# Power.net
KiCad netlist of a schematic drawn in Altium Designer
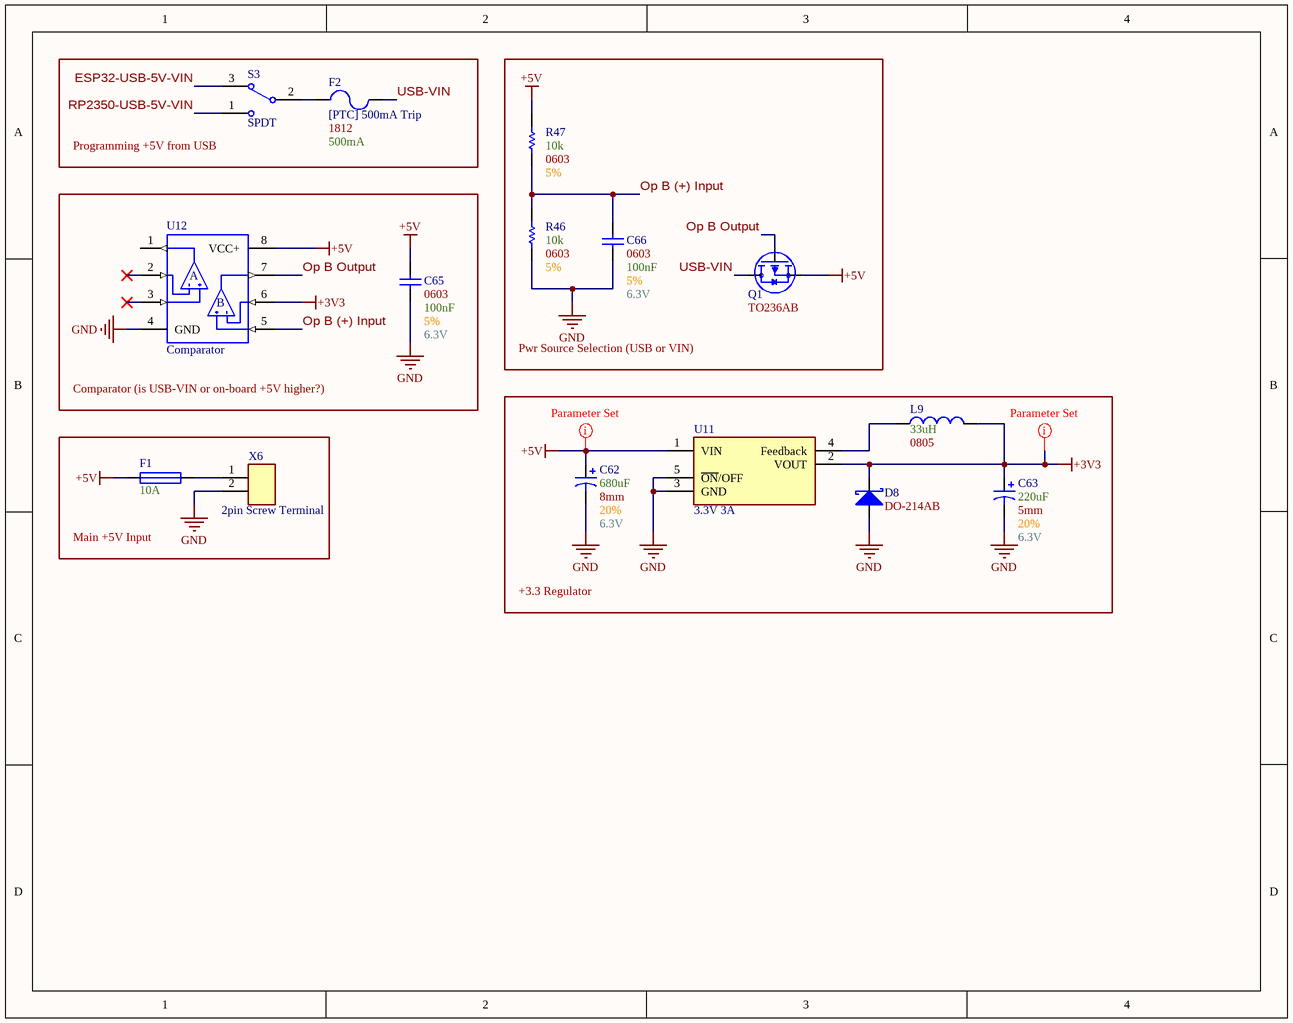
[diagram p0: Power.SchDoc]

(export (version "E")
  (design (tool "Eeschema 10.0.6"))
  (components
    (comp (ref "C62")
      (value "SMD Polarized")
      (footprint "[Cap] SMD Polarized, 8mm")
      (fields
        (field (name "TOLERANCE") "20%")
        (field (name "MAX VOLTAGE") "6.3V")
        (field (name "CAPACITANCE") "680uF")
        (field (name "DIAMETER") "8mm")
      )
      (libsource (lib "RADM Components") (part "[Cap] SMD Polarized"))
    )
    (comp (ref "C63")
      (value "SMD Polarized")
      (footprint "[Cap] SMD Polarized, 5mm")
      (fields
        (field (name "TOLERANCE") "20%")
        (field (name "MAX VOLTAGE") "6.3V")
        (field (name "CAPACITANCE") "220uF")
        (field (name "DIAMETER") "5mm")
      )
      (libsource (lib "RADM Components") (part "[Cap] SMD Polarized"))
    )
    (comp (ref "C65")
      (value "[Cap] SMD Nonpolarized")
      (footprint "[Cap] SMD 0603")
      (fields
        (field (name "SIZE PACKAGE") "0603")
        (field (name "CAPACITANCE") "100nF")
        (field (name "VOLTAGE") "6.3V")
        (field (name "TOLERANCE") "5%")
      )
      (libsource (lib "RADM Components") (part "[Cap] SMD Nonpolarized"))
    )
    (comp (ref "C66")
      (value "[Cap] SMD Nonpolarized")
      (footprint "[Cap] SMD 0603")
      (fields
        (field (name "SIZE PACKAGE") "0603")
        (field (name "CAPACITANCE") "100nF")
        (field (name "VOLTAGE") "6.3V")
        (field (name "TOLERANCE") "5%")
      )
      (libsource (lib "RADM Components") (part "[Cap] SMD Nonpolarized"))
    )
    (comp (ref "D8")
      (value "Schottky")
      (footprint "[Diode] SMD DO-214AB")
      (description "Generic")
      (fields (field (name "SIZE PACKAGE") "DO-214AB"))
      (libsource (lib "RADM Components") (part "[Diode] SMD Schottky"))
    )
    (comp (ref "F1")
      (value "Right-Angle")
      (footprint "[Fuse] Blade Right-Angle")
      (fields (field (name "AMPERAGE") "10A"))
      (libsource (lib "RADM Components") (part "[Fuse] Blade Right-Angle"))
    )
    (comp (ref "F2")
      (value "[PTC] 500mA Trip")
      (footprint "[PTC] 500mA Trip")
      (description "MF-MSMF050-2")
      (fields (field (name "SIZE PACKAGE") "1812") (field (name "TRIP CURRENT") "500mA"))
      (libsource (lib "RADM Components") (part "[PTC] 500mA Trip"))
    )
    (comp (ref "L9")
      (value "SMD Inductor")
      (footprint "[Inductor] SMD 0805")
      (fields (field (name "SIZE PACKAGE") "0805") (field (name "INDUCTANCE") "33uH"))
      (libsource (lib "RADM Components") (part "[Inductor] SMD Inductor"))
    )
    (comp (ref "Q1")
      (value "PMV48XP")
      (footprint "[FET] P-Channel Mosfet")
      (fields (field (name "SIZE PACKAGE") "TO236AB"))
      (libsource (lib "RADM Components") (part "[FET] P-Channel MOSFET"))
    )
    (comp (ref "R46")
      (value "[Res] SMD Resistor")
      (footprint "[Res] SMD 0603")
      (description "Generic")
      (fields
        (field (name "RESISTANCE") "10k")
        (field (name "SIZE PACKAGE") "0603")
        (field (name "TOLERANCE") "5%")
      )
      (libsource (lib "RADM Components") (part "[Res] SMD Resistor"))
    )
    (comp (ref "R47")
      (value "[Res] SMD Resistor")
      (footprint "[Res] SMD 0603")
      (description "Generic")
      (fields
        (field (name "RESISTANCE") "10k")
        (field (name "SIZE PACKAGE") "0603")
        (field (name "TOLERANCE") "5%")
      )
      (libsource (lib "RADM Components") (part "[Res] SMD Resistor"))
    )
    (comp (ref "S3")
      (value "SPDT")
      (footprint "[Switch] SPDT")
      (libsource (lib "RADM Components") (part "[Switch] SPDT Switch"))
    )
    (comp (ref "U11")
      (value "3.3V 3A")
      (footprint "[Reg] 3V3 Regulator (4)")
      (description "3A")
      (libsource (lib "RADM Components") (part "[Reg] 3V3 Regulator (4)"))
    )
    (comp (ref "U12")
      (value "Comparator")
      (footprint "[IC] Dual Op-Ap")
      (description "LMV358IDGKR")
      (libsource (lib "RADM Components") (part "[IC] Dual Op-Amp"))
    )
    (comp (ref "X6")
      (value "2pin Screw Terminal")
      (footprint "[Screw Terminal] 2pin 5mm")
      (libsource (lib "RADM Connectors") (part "[Screw Terminal] 2pin"))
    )
  )
  (nets
    (net (code "1") (name "+3V3") (class "Default")
      (node (ref "C63") (pin "1") (pinfunction "1_1") (pintype "passive"))
      (node (ref "D8") (pin "1") (pinfunction "K_1") (pintype "power_in"))
      (node (ref "L9") (pin "2") (pinfunction "2_2") (pintype "passive"))
      (node (ref "U11") (pin "2") (pinfunction "VOUT_2") (pintype "passive"))
      (node (ref "U12") (pin "6") (pinfunction "2IN-_6") (pintype "input"))
    )
    (net (code "2") (name "+5V") (class "Default")
      (node (ref "C62") (pin "1") (pinfunction "1_1") (pintype "passive"))
      (node (ref "C65") (pin "2") (pinfunction "2_2") (pintype "passive"))
      (node (ref "F1") (pin "1") (pinfunction "1_1") (pintype "passive"))
      (node (ref "Q1") (pin "2") (pinfunction "S_2") (pintype "passive"))
      (node (ref "R47") (pin "2") (pinfunction "2_2") (pintype "passive"))
      (node (ref "U11") (pin "1") (pinfunction "VIN_1") (pintype "passive"))
      (node (ref "U12") (pin "8") (pinfunction "VCC+_8") (pintype "power_in"))
    )
    (net (code "3") (name "/ESP32-USB-5V-VIN") (class "Default")
      (node (ref "S3") (pin "3") (pinfunction "3_3") (pintype "passive"))
    )
    (net (code "4") (name "/Op B (+) Input") (class "Default")
      (node (ref "C66") (pin "2") (pinfunction "2_2") (pintype "passive"))
      (node (ref "R46") (pin "2") (pinfunction "2_2") (pintype "passive"))
      (node (ref "R47") (pin "1") (pinfunction "1_1") (pintype "passive"))
      (node (ref "U12") (pin "5") (pinfunction "2IN+_5") (pintype "input"))
    )
    (net (code "5") (name "/Op B Output") (class "Default")
      (node (ref "Q1") (pin "1") (pinfunction "G_1") (pintype "passive"))
      (node (ref "U12") (pin "7") (pinfunction "2OUT_7") (pintype "output"))
    )
    (net (code "6") (name "/RP2350-USB-5V-VIN") (class "Default")
      (node (ref "S3") (pin "1") (pinfunction "1_1") (pintype "passive"))
    )
    (net (code "7") (name "/USB-VIN") (class "Default")
      (node (ref "F2") (pin "2") (pinfunction "2_2") (pintype "passive"))
      (node (ref "Q1") (pin "3") (pinfunction "D_3") (pintype "passive"))
    )
    (net (code "8") (name "GND") (class "Default")
      (node (ref "C62") (pin "2") (pinfunction "2_2") (pintype "passive"))
      (node (ref "C63") (pin "2") (pinfunction "2_2") (pintype "passive"))
      (node (ref "C65") (pin "1") (pinfunction "1_1") (pintype "passive"))
      (node (ref "C66") (pin "1") (pinfunction "1_1") (pintype "passive"))
      (node (ref "D8") (pin "2") (pinfunction "A_2") (pintype "power_in"))
      (node (ref "R46") (pin "1") (pinfunction "1_1") (pintype "passive"))
      (node (ref "U11") (pin "3") (pinfunction "GND_3") (pintype "passive"))
      (node (ref "U11") (pin "5") (pinfunction "~{ON}/OFF_5") (pintype "passive"))
      (node (ref "U12") (pin "4") (pinfunction "GND_4") (pintype "power_in"))
      (node (ref "X6") (pin "2") (pintype "power_in"))
    )
    (net (code "9") (name "Net-(F1-Pad2)") (class "Default")
      (node (ref "F1") (pin "2") (pinfunction "2_2") (pintype "passive"))
      (node (ref "X6") (pin "1") (pintype "power_in"))
    )
    (net (code "10") (name "Net-(F2-Pad1)") (class "Default")
      (node (ref "F2") (pin "1") (pinfunction "1_1") (pintype "passive"))
      (node (ref "S3") (pin "2") (pinfunction "2_2") (pintype "passive"))
    )
    (net (code "11") (name "Net-(U11-Feedback)") (class "Default")
      (node (ref "L9") (pin "1") (pinfunction "1_1") (pintype "passive"))
      (node (ref "U11") (pin "4") (pinfunction "Feedback_4") (pintype "passive"))
    )
    (net (code "12") (name "unconnected-(U12-1IN+-Pad3)") (class "Default")
      (node (ref "U12") (pin "3") (pinfunction "1IN+_3") (pintype "input+no_connect"))
    )
    (net (code "13") (name "unconnected-(U12-1IN--Pad2)") (class "Default")
      (node (ref "U12") (pin "2") (pinfunction "1IN-_2") (pintype "input+no_connect"))
    )
    (net (code "14") (name "unconnected-(U12-1OUT-Pad1)") (class "Default")
      (node (ref "U12") (pin "1") (pinfunction "1OUT_1") (pintype "output"))
    )
  )
)
